# PIC12F_boost_2021_09_29_A.net
KiCad netlist of a schematic drawn in EAGLE
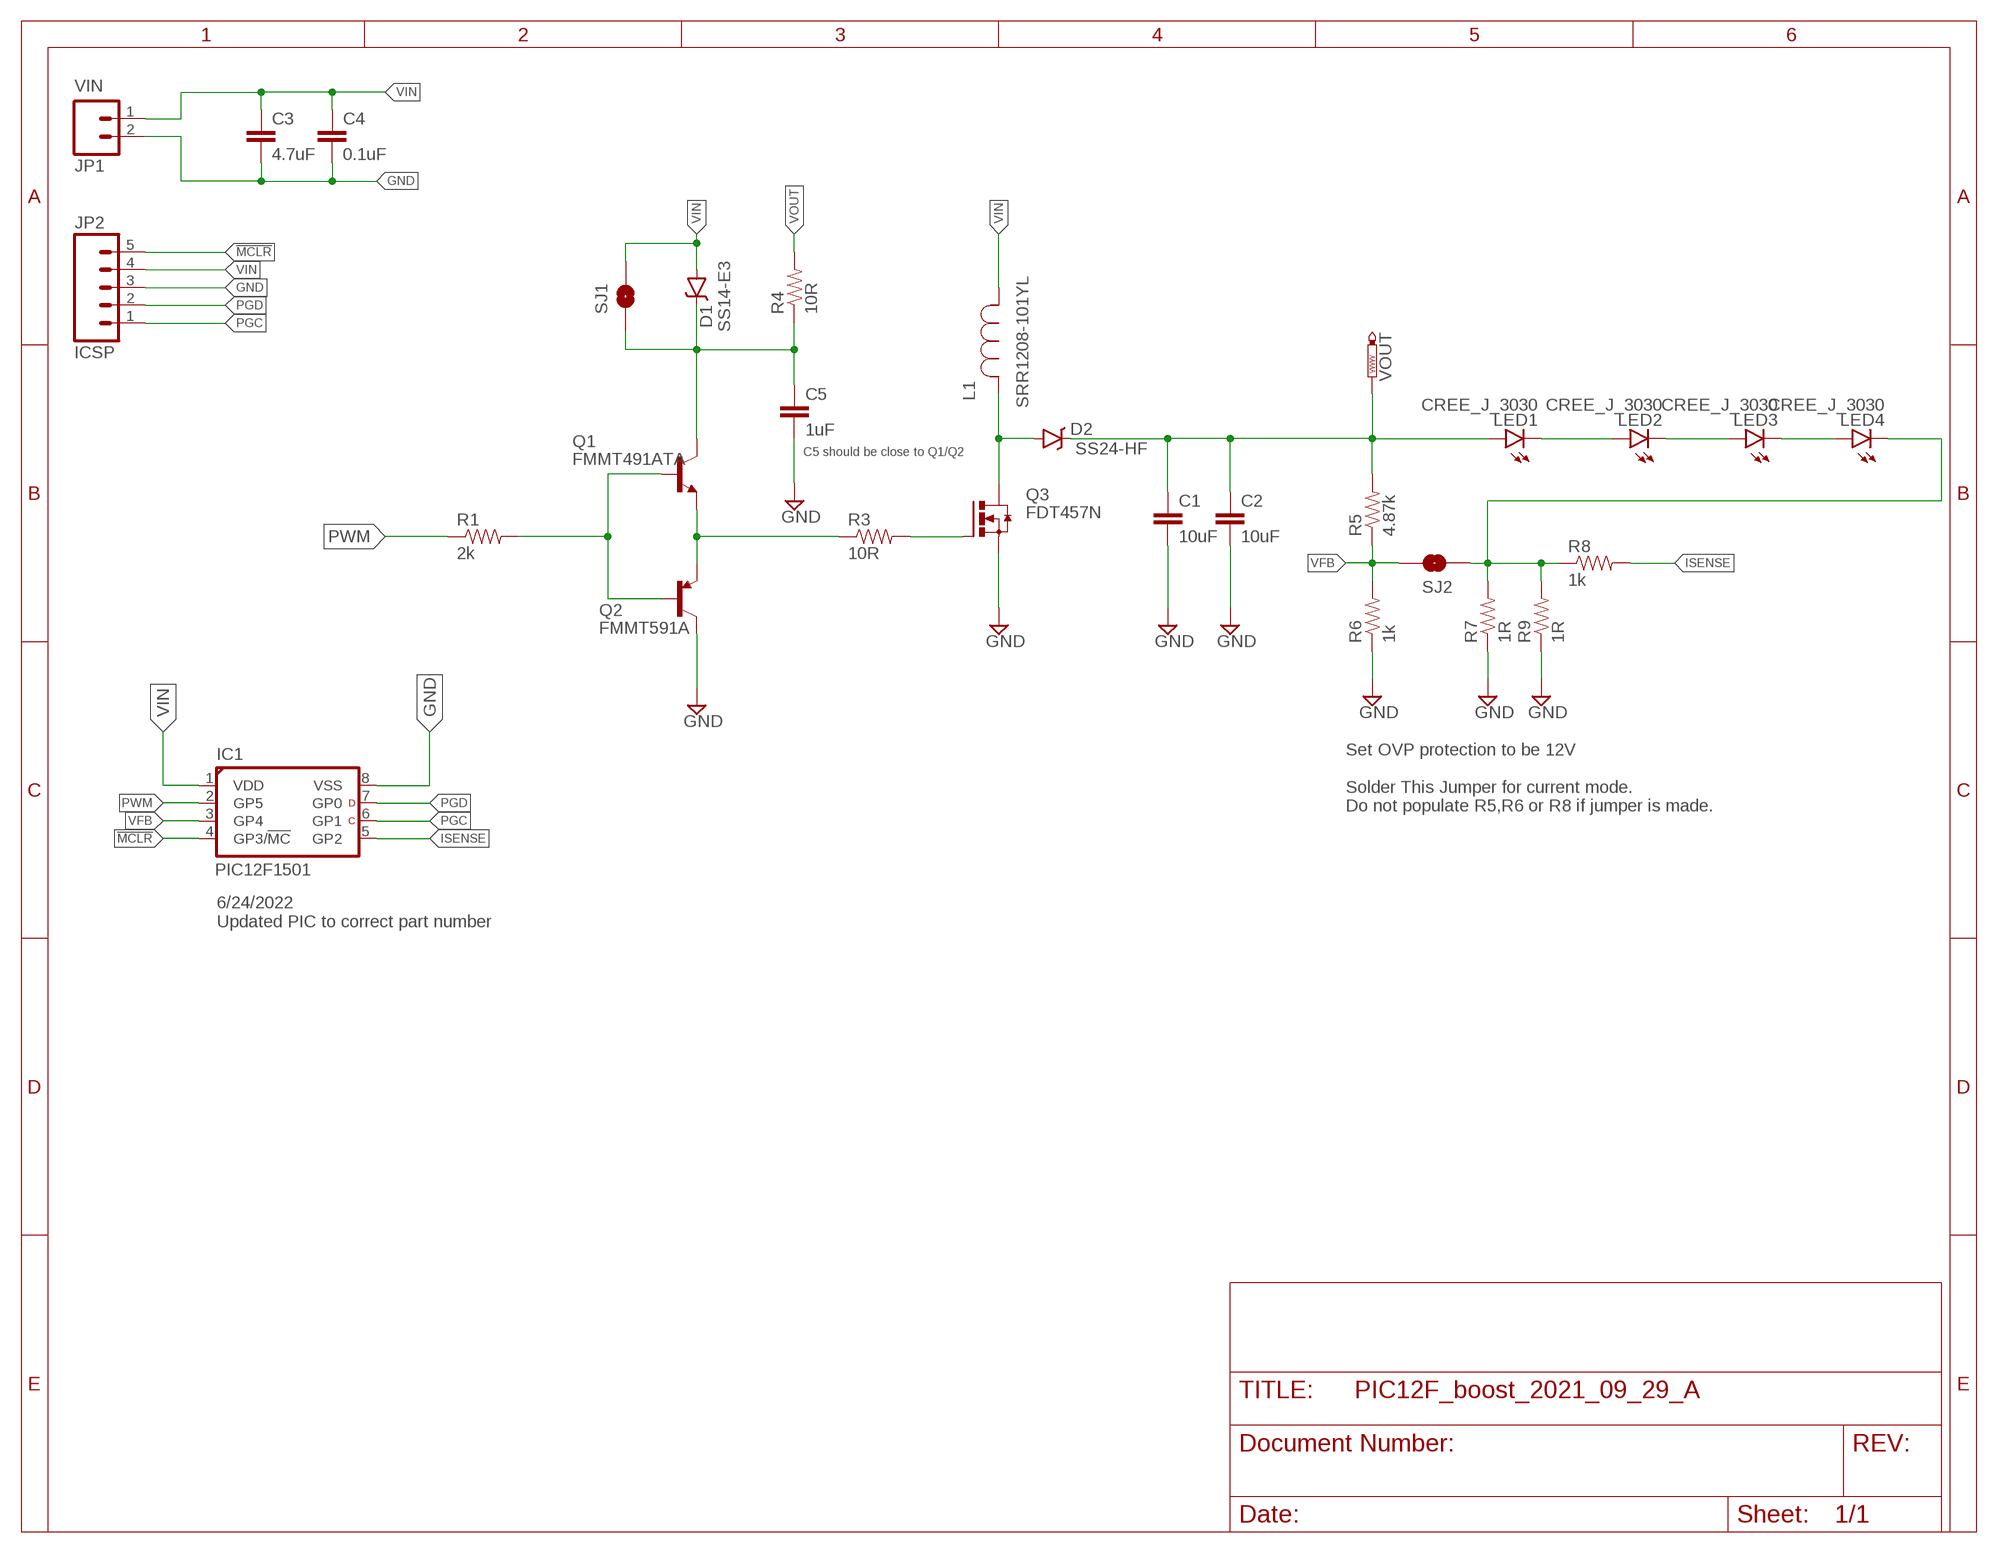
[diagram p0: schematic, sheet 1]

(export (version "E")
  (design (tool "Eeschema 10.0.6"))
  (components
    (comp (ref "C1")
      (value "10uF")
      (footprint "eagle-import:1206")
      (libsource (lib "eagle-import") (part "CAP1206"))
    )
    (comp (ref "C2")
      (value "10uF")
      (footprint "eagle-import:1206")
      (libsource (lib "eagle-import") (part "CAP1206"))
    )
    (comp (ref "C3")
      (value "4.7uF")
      (footprint "eagle-import:1206")
      (libsource (lib "eagle-import") (part "CAP1206"))
    )
    (comp (ref "C4")
      (value "0.1uF")
      (footprint "eagle-import:1206")
      (libsource (lib "eagle-import") (part "CAP1206"))
    )
    (comp (ref "C5")
      (value "1uF")
      (footprint "eagle-import:1206")
      (libsource (lib "eagle-import") (part "CAP1206"))
    )
    (comp (ref "D1")
      (value "SS14-E3")
      (footprint "eagle-import:SOD-323")
      (libsource (lib "eagle-import") (part "DIODE-SCHOTTKY-BAT20J"))
    )
    (comp (ref "D2")
      (value "SS24-HF")
      (footprint "eagle-import:SMA-DIODE")
      (libsource (lib "eagle-import") (part "DIODE-SCHOTTKY-MBRA140"))
    )
    (comp (ref "IC1")
      (value "PIC12F1501")
      (footprint "eagle-import:SOIC8-SN")
      (libsource (lib "eagle-import") (part "PIC12F510/SN"))
    )
    (comp (ref "JP1")
      (value "M02POLAR_LOCK")
      (footprint "eagle-import:MOLEX-1X2_LOCK")
      (libsource (lib "eagle-import") (part "M02POLAR_LOCK"))
    )
    (comp (ref "JP2")
      (value "ICSP")
      (footprint "eagle-import:1X05_LOCK_LONGPADS")
      (libsource (lib "eagle-import") (part "M05LOCK_LONGPADS"))
    )
    (comp (ref "L1")
      (value "SRR1208-101YL")
      (footprint "eagle-import:IND_BOURNS_SRR1208")
      (fields (field (name "COPYRIGHT") "Copyright (C) 2021 Ultra Librarian. All rights reserved."))
      (libsource (lib "eagle-import") (part "SRR1208-101YL"))
    )
    (comp (ref "LED1")
      (value "CREE_J_3030")
      (footprint "eagle-import:CREE_J_3030")
      (libsource (lib "eagle-import") (part "CREE_J_3030"))
    )
    (comp (ref "LED2")
      (value "CREE_J_3030")
      (footprint "eagle-import:CREE_J_3030")
      (libsource (lib "eagle-import") (part "CREE_J_3030"))
    )
    (comp (ref "LED3")
      (value "CREE_J_3030")
      (footprint "eagle-import:CREE_J_3030")
      (libsource (lib "eagle-import") (part "CREE_J_3030"))
    )
    (comp (ref "LED4")
      (value "CREE_J_3030")
      (footprint "eagle-import:CREE_J_3030")
      (libsource (lib "eagle-import") (part "CREE_J_3030"))
    )
    (comp (ref "Q1")
      (value "FMMT491ATA")
      (footprint "eagle-import:SOT23")
      (libsource (lib "eagle-import") (part "TRANSISTOR_NPNMMBT5088"))
    )
    (comp (ref "Q2")
      (value "FMMT591A")
      (footprint "eagle-import:SOT23")
      (libsource (lib "eagle-import") (part "TRANSISTOR_PNPMMBT4403"))
    )
    (comp (ref "Q3")
      (value "FDT457N")
      (footprint "eagle-import:SOT223")
      (libsource (lib "eagle-import") (part "N-HEXFET_?-SOT323"))
    )
    (comp (ref "R1")
      (value "2k")
      (footprint "eagle-import:1206")
      (libsource (lib "eagle-import") (part "RESISTOR1206"))
    )
    (comp (ref "R3")
      (value "10R")
      (footprint "eagle-import:1206")
      (libsource (lib "eagle-import") (part "RESISTOR1206"))
    )
    (comp (ref "R4")
      (value "10R")
      (footprint "eagle-import:1206")
      (libsource (lib "eagle-import") (part "RESISTOR1206"))
    )
    (comp (ref "R5")
      (value "4.87k")
      (footprint "eagle-import:1206")
      (libsource (lib "eagle-import") (part "RESISTOR1206"))
    )
    (comp (ref "R6")
      (value "1k")
      (footprint "eagle-import:1206")
      (libsource (lib "eagle-import") (part "RESISTOR1206"))
    )
    (comp (ref "R7")
      (value "1R")
      (footprint "eagle-import:1206")
      (libsource (lib "eagle-import") (part "RESISTOR1206"))
    )
    (comp (ref "R8")
      (value "1k")
      (footprint "eagle-import:1206")
      (libsource (lib "eagle-import") (part "RESISTOR1206"))
    )
    (comp (ref "R9")
      (value "1R")
      (footprint "eagle-import:1206")
      (libsource (lib "eagle-import") (part "RESISTOR1206"))
    )
    (comp (ref "SJ1")
      (value "SPARKFUN_SOLDERJUMPERNO")
      (footprint "eagle-import:SPARKFUN_SJ_2S-NO")
      (libsource (lib "eagle-import") (part "SPARKFUN_SOLDERJUMPERNO"))
    )
    (comp (ref "SJ2")
      (value "SPARKFUN_SOLDERJUMPERNO")
      (footprint "eagle-import:SPARKFUN_SJ_2S-NO")
      (libsource (lib "eagle-import") (part "SPARKFUN_SOLDERJUMPERNO"))
    )
    (comp (ref "VOUT")
      (value "PTR1TP20R")
      (footprint "eagle-import:TP20R")
      (libsource (lib "eagle-import") (part "PTR1TP20R"))
    )
  )
  (nets
    (net (code "1") (name "/~{MCLR}") (class "Default")
      (node (ref "IC1") (pin "4") (pinfunction "GP3/~{MC}_4") (pintype "bidirectional"))
      (node (ref "JP2") (pin "5") (pinfunction "5_5") (pintype "passive"))
    )
    (net (code "2") (name "GND") (class "Default")
      (node (ref "C1") (pin "2") (pinfunction "2_2") (pintype "passive"))
      (node (ref "C2") (pin "2") (pinfunction "2_2") (pintype "passive"))
      (node (ref "C3") (pin "2") (pinfunction "2_2") (pintype "passive"))
      (node (ref "C4") (pin "2") (pinfunction "2_2") (pintype "passive"))
      (node (ref "C5") (pin "2") (pinfunction "2_2") (pintype "passive"))
      (node (ref "IC1") (pin "8") (pinfunction "VSS_8") (pintype "passive"))
      (node (ref "JP1") (pin "2") (pinfunction "2_2") (pintype "passive"))
      (node (ref "JP2") (pin "3") (pinfunction "3_3") (pintype "passive"))
      (node (ref "Q2") (pin "3") (pinfunction "C_3") (pintype "passive"))
      (node (ref "Q3") (pin "3") (pinfunction "S_3") (pintype "passive"))
      (node (ref "R6") (pin "1") (pinfunction "1_1") (pintype "passive"))
      (node (ref "R7") (pin "1") (pinfunction "1_1") (pintype "passive"))
      (node (ref "R9") (pin "1") (pinfunction "1_1") (pintype "passive"))
    )
    (net (code "3") (name "ISENSE") (class "Default")
      (node (ref "IC1") (pin "5") (pinfunction "GP2_5") (pintype "bidirectional"))
      (node (ref "R8") (pin "2") (pinfunction "2_2") (pintype "passive"))
    )
    (net (code "4") (name "Net-(LED1-PadC)") (class "Default")
      (node (ref "LED1") (pin "C") (pinfunction "C_C") (pintype "passive"))
      (node (ref "LED2") (pin "A") (pinfunction "A_A") (pintype "passive"))
      (node (ref "LED2") (pin "A2") (pinfunction "A_A2") (pintype "passive"))
    )
    (net (code "5") (name "Net-(LED2-PadC)") (class "Default")
      (node (ref "LED2") (pin "C") (pinfunction "C_C") (pintype "passive"))
      (node (ref "LED3") (pin "A") (pinfunction "A_A") (pintype "passive"))
      (node (ref "LED3") (pin "A2") (pinfunction "A_A2") (pintype "passive"))
    )
    (net (code "6") (name "Net-(LED3-PadC)") (class "Default")
      (node (ref "LED3") (pin "C") (pinfunction "C_C") (pintype "passive"))
      (node (ref "LED4") (pin "A") (pinfunction "A_A") (pintype "passive"))
      (node (ref "LED4") (pin "A2") (pinfunction "A_A2") (pintype "passive"))
    )
    (net (code "7") (name "Net-(LED4-PadC)") (class "Default")
      (node (ref "LED4") (pin "C") (pinfunction "C_C") (pintype "passive"))
      (node (ref "R7") (pin "2") (pinfunction "2_2") (pintype "passive"))
      (node (ref "R8") (pin "1") (pinfunction "1_1") (pintype "passive"))
      (node (ref "R9") (pin "2") (pinfunction "2_2") (pintype "passive"))
      (node (ref "SJ2") (pin "1") (pinfunction "1_1") (pintype "passive"))
    )
    (net (code "8") (name "Net-(Q1-B)") (class "Default")
      (node (ref "Q1") (pin "1") (pinfunction "B_1") (pintype "passive"))
      (node (ref "Q2") (pin "1") (pinfunction "B_1") (pintype "passive"))
      (node (ref "R1") (pin "2") (pinfunction "2_2") (pintype "passive"))
    )
    (net (code "9") (name "Net-(Q1-C)") (class "Default")
      (node (ref "C5") (pin "1") (pinfunction "1_1") (pintype "passive"))
      (node (ref "D1") (pin "C") (pinfunction "C_C") (pintype "passive"))
      (node (ref "Q1") (pin "3") (pinfunction "C_3") (pintype "passive"))
      (node (ref "R4") (pin "1") (pinfunction "1_1") (pintype "passive"))
      (node (ref "SJ1") (pin "1") (pinfunction "1_1") (pintype "passive"))
    )
    (net (code "10") (name "Net-(Q1-E)") (class "Default")
      (node (ref "Q1") (pin "2") (pinfunction "E_2") (pintype "passive"))
      (node (ref "Q2") (pin "2") (pinfunction "E_2") (pintype "passive"))
      (node (ref "R3") (pin "1") (pinfunction "1_1") (pintype "passive"))
    )
    (net (code "11") (name "Net-(Q3-D)") (class "Default")
      (node (ref "D2") (pin "A") (pinfunction "A_A") (pintype "passive"))
      (node (ref "L1") (pin "2") (pinfunction "2_2") (pintype "passive"))
      (node (ref "Q3") (pin "4") (pinfunction "D_4") (pintype "passive"))
    )
    (net (code "12") (name "Net-(Q3-G)") (class "Default")
      (node (ref "Q3") (pin "1") (pinfunction "G_1") (pintype "passive"))
      (node (ref "R3") (pin "2") (pinfunction "2_2") (pintype "passive"))
    )
    (net (code "13") (name "PGC") (class "Default")
      (node (ref "IC1") (pin "6") (pinfunction "GP1_6") (pintype "bidirectional"))
      (node (ref "JP2") (pin "1") (pinfunction "1_1") (pintype "passive"))
    )
    (net (code "14") (name "PGD") (class "Default")
      (node (ref "IC1") (pin "7") (pinfunction "GP0_7") (pintype "bidirectional"))
      (node (ref "JP2") (pin "2") (pinfunction "2_2") (pintype "passive"))
    )
    (net (code "15") (name "PWM") (class "Default")
      (node (ref "IC1") (pin "2") (pinfunction "GP5_2") (pintype "bidirectional"))
      (node (ref "R1") (pin "1") (pinfunction "1_1") (pintype "passive"))
    )
    (net (code "16") (name "VFB") (class "Default")
      (node (ref "IC1") (pin "3") (pinfunction "GP4_3") (pintype "bidirectional"))
      (node (ref "R5") (pin "1") (pinfunction "1_1") (pintype "passive"))
      (node (ref "R6") (pin "2") (pinfunction "2_2") (pintype "passive"))
      (node (ref "SJ2") (pin "2") (pinfunction "2_2") (pintype "passive"))
    )
    (net (code "17") (name "VIN") (class "Default")
      (node (ref "C3") (pin "1") (pinfunction "1_1") (pintype "passive"))
      (node (ref "C4") (pin "1") (pinfunction "1_1") (pintype "passive"))
      (node (ref "D1") (pin "A") (pinfunction "A_A") (pintype "passive"))
      (node (ref "IC1") (pin "1") (pinfunction "VDD_1") (pintype "passive"))
      (node (ref "JP1") (pin "1") (pinfunction "1_1") (pintype "passive"))
      (node (ref "JP2") (pin "4") (pinfunction "4_4") (pintype "passive"))
      (node (ref "L1") (pin "1") (pinfunction "1_1") (pintype "passive"))
      (node (ref "SJ1") (pin "2") (pinfunction "2_2") (pintype "passive"))
    )
    (net (code "18") (name "VOUT") (class "Default")
      (node (ref "C1") (pin "1") (pinfunction "1_1") (pintype "passive"))
      (node (ref "C2") (pin "1") (pinfunction "1_1") (pintype "passive"))
      (node (ref "D2") (pin "C") (pinfunction "C_C") (pintype "passive"))
      (node (ref "LED1") (pin "A") (pinfunction "A_A") (pintype "passive"))
      (node (ref "LED1") (pin "A2") (pinfunction "A_A2") (pintype "passive"))
      (node (ref "R4") (pin "2") (pinfunction "2_2") (pintype "passive"))
      (node (ref "R5") (pin "2") (pinfunction "2_2") (pintype "passive"))
      (node (ref "VOUT") (pin "TP") (pinfunction "TP_TP") (pintype "input"))
    )
  )
)
